# blds.net
KiCad netlist of a schematic drawn in Altium Designer
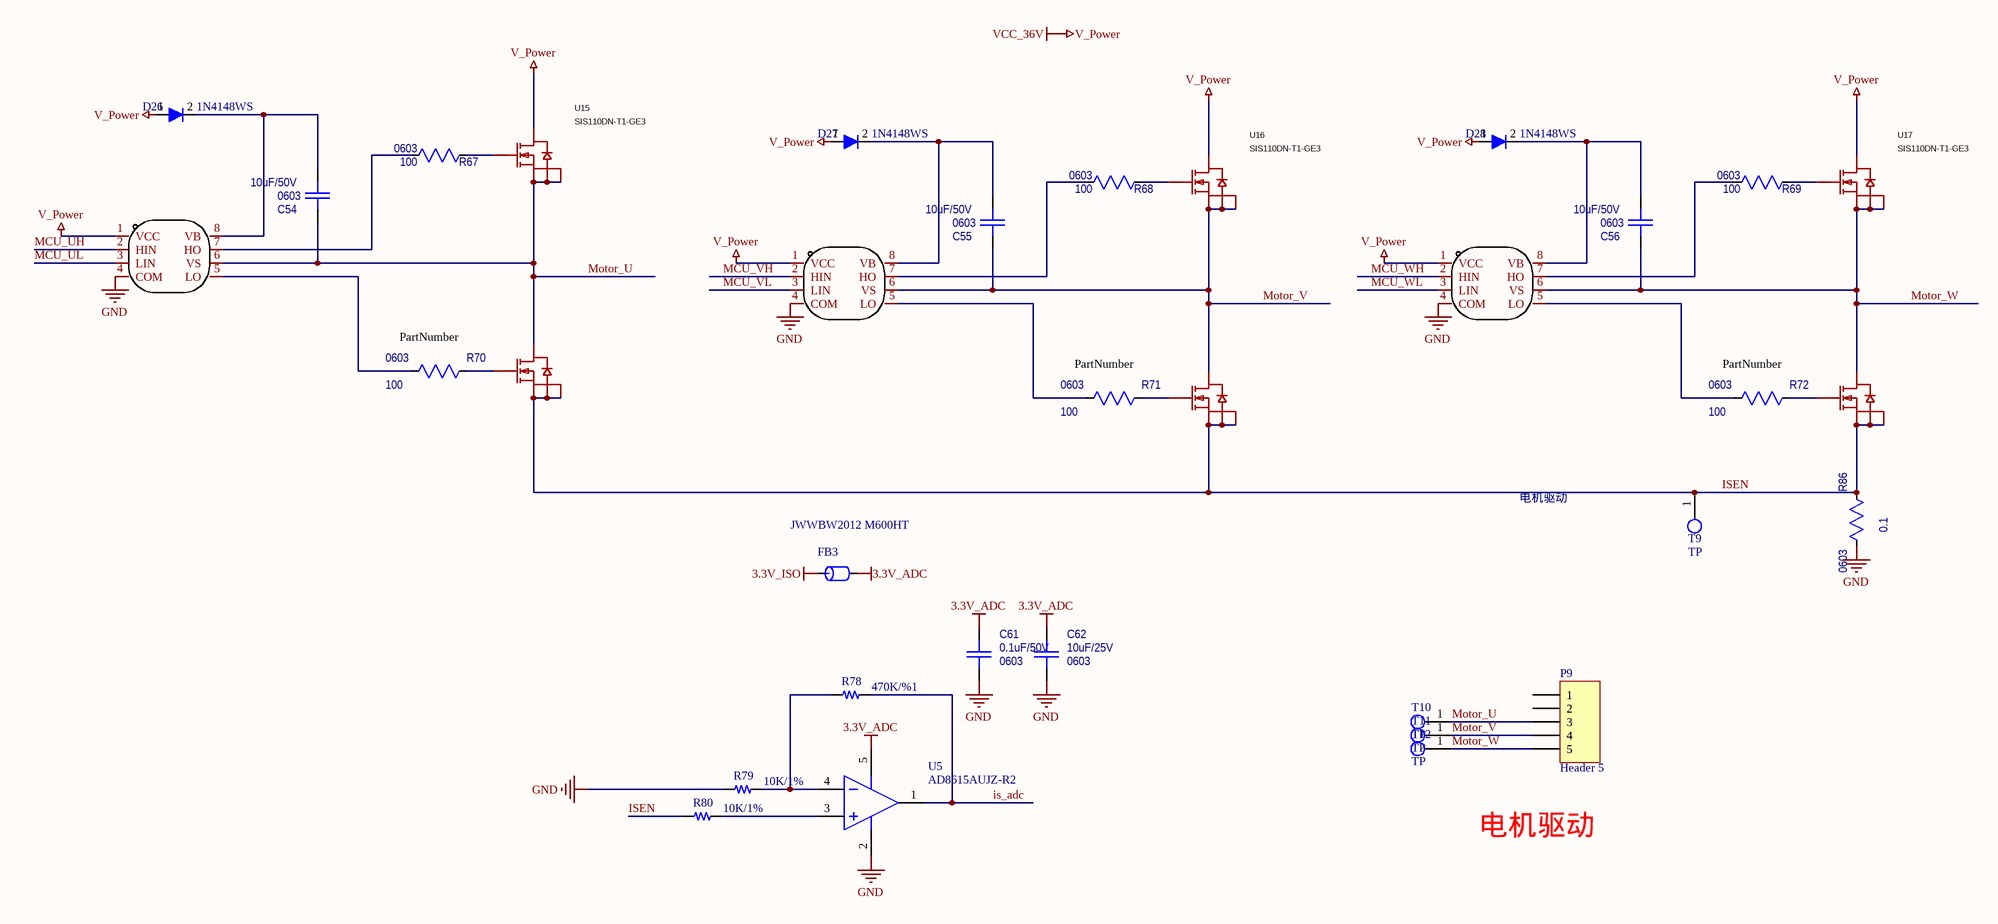
[diagram p0: blds.SchDoc]

(export (version "E")
  (design (tool "Eeschema 10.0.6"))
  (components
    (comp (ref "C54")
      (value "10uF/50V")
      (footprint "CAPC1608X092N_0603")
      (description "Capacitor, MLCC")
      (fields
        (field (name "MANUFACTURER") "muRata")
        (field (name "PARTNUMBER") "GQM2195C2E4R7CB12J")
        (field (name "PACKAGE") "0603")
      )
      (libsource (lib "Karl") (part "Capacitor_0603"))
    )
    (comp (ref "C55")
      (value "10uF/50V")
      (footprint "CAPC1608X092N_0603")
      (description "Capacitor, MLCC")
      (fields
        (field (name "MANUFACTURER") "muRata")
        (field (name "PARTNUMBER") "GQM2195C2E4R7CB12J")
        (field (name "PACKAGE") "0603")
      )
      (libsource (lib "Karl") (part "Capacitor_0603"))
    )
    (comp (ref "C56")
      (value "10uF/50V")
      (footprint "CAPC1608X092N_0603")
      (description "Capacitor, MLCC")
      (fields
        (field (name "MANUFACTURER") "muRata")
        (field (name "PARTNUMBER") "GQM2195C2E4R7CB12J")
        (field (name "PACKAGE") "0603")
      )
      (libsource (lib "Karl") (part "Capacitor_0603"))
    )
    (comp (ref "C61")
      (value "0.1uF/50V")
      (footprint "CAPC1608X092N_0603")
      (fields
        (field (name "PARTNUMBER") "C0603C104M5RACTU")
        (field (name "TOLERANCE") "[tol]")
        (field (name "PACKAGE") "0603")
        (field (name "Comment") "Capacitor_0603")
      )
      (libsource (lib "Karl") (part "Capacitor_0603"))
    )
    (comp (ref "C62")
      (value "10uF/25V")
      (footprint "CAPC1608X092N_0603")
      (fields
        (field (name "PARTNUMBER") "C0603C104M5RACTU")
        (field (name "TOLERANCE") "[tol]")
        (field (name "PACKAGE") "0603")
        (field (name "Comment") "Capacitor_0603")
      )
      (libsource (lib "Karl") (part "Capacitor_0603"))
    )
    (comp (ref "D26") (value "1N4148WS") (footprint "SOD323") (libsource (lib "Device2018") (part "LL4148")))
    (comp (ref "D27") (value "1N4148WS") (footprint "SOD323") (libsource (lib "Device2018") (part "LL4148")))
    (comp (ref "D28") (value "1N4148WS") (footprint "SOD323") (libsource (lib "Device2018") (part "LL4148")))
    (comp (ref "FB3")
      (value "JWWBW2012 M600HT")
      (footprint "0805R")
      (libsource (lib "Schlib_20110825") (part "FB"))
    )
    (comp (ref "P9")
      (value "Header 5")
      (footprint "HDR1X5")
      (description "Header, 5-Pin")
      (fields (field (name "PUBLISHER") "Altium Limited"))
      (libsource (lib "Miscellaneous Connectors") (part "Header 5"))
    )
    (comp (ref "R67")
      (value "100")
      (footprint "RESC1608X055N_0603")
      (description "Resistor, Standard")
      (fields
        (field (name "MANUFACTURER") "Yageo")
        (field (name "PARTNUMBER") "RC0603FR-0710KL")
        (field (name "PACKAGE") "0603")
      )
      (libsource (lib "Karl") (part "Resistor_0603"))
    )
    (comp (ref "R68")
      (value "100")
      (footprint "RESC1608X055N_0603")
      (description "Resistor, Standard")
      (fields
        (field (name "MANUFACTURER") "Yageo")
        (field (name "PARTNUMBER") "RC0603FR-0710KL")
        (field (name "PACKAGE") "0603")
      )
      (libsource (lib "Karl") (part "Resistor_0603"))
    )
    (comp (ref "R69")
      (value "100")
      (footprint "RESC1608X055N_0603")
      (description "Resistor, Standard")
      (fields
        (field (name "MANUFACTURER") "Yageo")
        (field (name "PARTNUMBER") "RC0603FR-0710KL")
        (field (name "PACKAGE") "0603")
      )
      (libsource (lib "Karl") (part "Resistor_0603"))
    )
    (comp (ref "R70")
      (value "100")
      (footprint "RESC1608X055N_0603")
      (description "Resistor, Standard")
      (fields
        (field (name "MANUFACTURER") "Yageo")
        (field (name "PARTNUMBER") "RC0603FR-0710KL")
        (field (name "PACKAGE") "0603")
      )
      (libsource (lib "Karl") (part "Resistor_0603"))
    )
    (comp (ref "R71")
      (value "100")
      (footprint "RESC1608X055N_0603")
      (description "Resistor, Standard")
      (fields
        (field (name "MANUFACTURER") "Yageo")
        (field (name "PARTNUMBER") "RC0603FR-0710KL")
        (field (name "PACKAGE") "0603")
      )
      (libsource (lib "Karl") (part "Resistor_0603"))
    )
    (comp (ref "R72")
      (value "100")
      (footprint "RESC1608X055N_0603")
      (description "Resistor, Standard")
      (fields
        (field (name "MANUFACTURER") "Yageo")
        (field (name "PARTNUMBER") "RC0603FR-0710KL")
        (field (name "PACKAGE") "0603")
      )
      (libsource (lib "Karl") (part "Resistor_0603"))
    )
    (comp (ref "R78") (value "470K/%1") (footprint "0603R") (libsource (lib "JRJ_1") (part "R")))
    (comp (ref "R79") (value "10K/1%") (footprint "0603R") (libsource (lib "JRJ_1") (part "R")))
    (comp (ref "R80") (value "10K/1%") (footprint "0603R") (libsource (lib "JRJ_1") (part "R")))
    (comp (ref "R86")
      (value "0.1")
      (footprint "2010R")
      (description "Resistor, Standard")
      (fields
        (field (name "MANUFACTURER") "Yageo")
        (field (name "PARTNUMBER") "RC0603FR-0710KL")
        (field (name "PACKAGE") "0603")
      )
      (libsource (lib "Karl") (part "Resistor_0603"))
    )
    (comp (ref "T9") (value "TP") (footprint "TPD") (libsource (lib "Schlib_20110825") (part "TP")))
    (comp (ref "T10") (value "TP") (footprint "TPD") (libsource (lib "Schlib_20110825") (part "TP")))
    (comp (ref "T11") (value "TP") (footprint "TPD") (libsource (lib "Schlib_20110825") (part "TP")))
    (comp (ref "T12") (value "TP") (footprint "TPD") (libsource (lib "Schlib_20110825") (part "TP")))
    (comp (ref "U5")
      (value "AD8615AUJZ-R2")
      (footprint "sot-23-5")
      (libsource (lib "Schlib_20110825") (part "AD8615"))
    )
    (comp (ref "U15")
      (value "SIS110DN-T1-GE3")
      (footprint "DFN-8_L3.3-W3.3-P0.65-BL-2")
      (fields (field (name "MANUFACTURER") "VISHAY(威世)"))
      (libsource (lib "altium-import") (part "root_0_SIS110DN-T1-GE3_"))
    )
    (comp (ref "U16")
      (value "SIS110DN-T1-GE3")
      (footprint "DFN-8_L3.3-W3.3-P0.65-BL-2")
      (fields (field (name "MANUFACTURER") "VISHAY(威世)"))
      (libsource (lib "altium-import") (part "root_0_SIS110DN-T1-GE3_"))
    )
    (comp (ref "U17")
      (value "SIS110DN-T1-GE3")
      (footprint "DFN-8_L3.3-W3.3-P0.65-BL-2")
      (fields (field (name "MANUFACTURER") "VISHAY(威世)"))
      (libsource (lib "altium-import") (part "root_0_SIS110DN-T1-GE3_"))
    )
    (comp (ref "U18")
      (value "IRS21867STRPBF")
      (footprint "SO-8")
      (fields (field (name "MANUFACTURER") "Infineon(英飞凌)"))
      (libsource (lib "altium-import") (part "root_0_IRS21867STRPBF_"))
    )
    (comp (ref "U19")
      (value "IRS21867STRPBF")
      (footprint "SO-8")
      (fields (field (name "MANUFACTURER") "Infineon(英飞凌)"))
      (libsource (lib "altium-import") (part "root_0_IRS21867STRPBF_"))
    )
    (comp (ref "U20")
      (value "IRS21867STRPBF")
      (footprint "SO-8")
      (fields (field (name "MANUFACTURER") "Infineon(英飞凌)"))
      (libsource (lib "altium-import") (part "root_0_IRS21867STRPBF_"))
    )
    (comp (ref "U21")
      (value "SIS110DN-T1-GE3")
      (footprint "DFN-8_L3.3-W3.3-P0.65-BL-2")
      (fields (field (name "MANUFACTURER") "VISHAY(威世)"))
      (libsource (lib "altium-import") (part "root_0_SIS110DN-T1-GE3_"))
    )
    (comp (ref "U22")
      (value "SIS110DN-T1-GE3")
      (footprint "DFN-8_L3.3-W3.3-P0.65-BL-2")
      (fields (field (name "MANUFACTURER") "VISHAY(威世)"))
      (libsource (lib "altium-import") (part "root_0_SIS110DN-T1-GE3_"))
    )
    (comp (ref "U23")
      (value "SIS110DN-T1-GE3")
      (footprint "DFN-8_L3.3-W3.3-P0.65-BL-2")
      (fields (field (name "MANUFACTURER") "VISHAY(威世)"))
      (libsource (lib "altium-import") (part "root_0_SIS110DN-T1-GE3_"))
    )
  )
  (nets
    (net (code "1") (name "/ISEN") (class "Default")
      (node (ref "R80") (pin "2") (pintype "passive"))
      (node (ref "R86") (pin "2") (pinfunction "2_2") (pintype "passive"))
      (node (ref "T9") (pin "1") (pintype "passive"))
      (node (ref "U21") (pin "1") (pinfunction "S_1") (pintype "passive"))
      (node (ref "U21") (pin "2") (pinfunction "S_2") (pintype "passive"))
      (node (ref "U21") (pin "3") (pinfunction "S_3") (pintype "passive"))
      (node (ref "U22") (pin "1") (pinfunction "S_1") (pintype "passive"))
      (node (ref "U22") (pin "2") (pinfunction "S_2") (pintype "passive"))
      (node (ref "U22") (pin "3") (pinfunction "S_3") (pintype "passive"))
      (node (ref "U23") (pin "1") (pinfunction "S_1") (pintype "passive"))
      (node (ref "U23") (pin "2") (pinfunction "S_2") (pintype "passive"))
      (node (ref "U23") (pin "3") (pinfunction "S_3") (pintype "passive"))
    )
    (net (code "2") (name "/MCU_UH") (class "Default")
      (node (ref "U18") (pin "2") (pinfunction "HIN_2") (pintype "passive"))
    )
    (net (code "3") (name "/MCU_UL") (class "Default")
      (node (ref "U18") (pin "3") (pinfunction "LIN_3") (pintype "passive"))
    )
    (net (code "4") (name "/MCU_VH") (class "Default")
      (node (ref "U19") (pin "2") (pinfunction "HIN_2") (pintype "passive"))
    )
    (net (code "5") (name "/MCU_VL") (class "Default")
      (node (ref "U19") (pin "3") (pinfunction "LIN_3") (pintype "passive"))
    )
    (net (code "6") (name "/MCU_WH") (class "Default")
      (node (ref "U20") (pin "2") (pinfunction "HIN_2") (pintype "passive"))
    )
    (net (code "7") (name "/MCU_WL") (class "Default")
      (node (ref "U20") (pin "3") (pinfunction "LIN_3") (pintype "passive"))
    )
    (net (code "8") (name "/Motor_U") (class "Default")
      (node (ref "C54") (pin "1") (pinfunction "1_1") (pintype "passive"))
      (node (ref "P9") (pin "3") (pinfunction "3_3") (pintype "passive"))
      (node (ref "T10") (pin "1") (pintype "passive"))
      (node (ref "U15") (pin "1") (pinfunction "S_1") (pintype "passive"))
      (node (ref "U15") (pin "2") (pinfunction "S_2") (pintype "passive"))
      (node (ref "U15") (pin "3") (pinfunction "S_3") (pintype "passive"))
      (node (ref "U18") (pin "6") (pinfunction "VS_6") (pintype "passive"))
      (node (ref "U21") (pin "5") (pinfunction "D_5") (pintype "passive"))
    )
    (net (code "9") (name "/Motor_V") (class "Default")
      (node (ref "C55") (pin "1") (pinfunction "1_1") (pintype "passive"))
      (node (ref "P9") (pin "4") (pinfunction "4_4") (pintype "passive"))
      (node (ref "T11") (pin "1") (pintype "passive"))
      (node (ref "U16") (pin "1") (pinfunction "S_1") (pintype "passive"))
      (node (ref "U16") (pin "2") (pinfunction "S_2") (pintype "passive"))
      (node (ref "U16") (pin "3") (pinfunction "S_3") (pintype "passive"))
      (node (ref "U19") (pin "6") (pinfunction "VS_6") (pintype "passive"))
      (node (ref "U22") (pin "5") (pinfunction "D_5") (pintype "passive"))
    )
    (net (code "10") (name "/Motor_W") (class "Default")
      (node (ref "C56") (pin "1") (pinfunction "1_1") (pintype "passive"))
      (node (ref "P9") (pin "5") (pinfunction "5_5") (pintype "passive"))
      (node (ref "T12") (pin "1") (pintype "passive"))
      (node (ref "U17") (pin "1") (pinfunction "S_1") (pintype "passive"))
      (node (ref "U17") (pin "2") (pinfunction "S_2") (pintype "passive"))
      (node (ref "U17") (pin "3") (pinfunction "S_3") (pintype "passive"))
      (node (ref "U20") (pin "6") (pinfunction "VS_6") (pintype "passive"))
      (node (ref "U23") (pin "5") (pinfunction "D_5") (pintype "passive"))
    )
    (net (code "11") (name "/is_adc") (class "Default")
      (node (ref "R78") (pin "1") (pintype "passive"))
      (node (ref "U5") (pin "1") (pinfunction "OS_NUL_1") (pintype "passive"))
    )
    (net (code "12") (name "3.3V_ADC") (class "Default")
      (node (ref "C61") (pin "1") (pinfunction "1_1") (pintype "passive"))
      (node (ref "C62") (pin "1") (pinfunction "1_1") (pintype "passive"))
      (node (ref "FB3") (pin "2") (pintype "passive"))
      (node (ref "U5") (pin "5") (pinfunction "VCC_5") (pintype "passive"))
    )
    (net (code "13") (name "3.3V_ISO") (class "Default") (node (ref "FB3") (pin "1") (pintype "passive")))
    (net (code "14") (name "GND") (class "Default")
      (node (ref "C61") (pin "2") (pinfunction "2_2") (pintype "passive"))
      (node (ref "C62") (pin "2") (pinfunction "2_2") (pintype "passive"))
      (node (ref "R79") (pin "2") (pintype "passive"))
      (node (ref "R86") (pin "1") (pinfunction "1_1") (pintype "passive"))
      (node (ref "U18") (pin "4") (pinfunction "COM_4") (pintype "passive"))
      (node (ref "U19") (pin "4") (pinfunction "COM_4") (pintype "passive"))
      (node (ref "U20") (pin "4") (pinfunction "COM_4") (pintype "passive"))
      (node (ref "U5") (pin "2") (pinfunction "G_2") (pintype "power_in"))
    )
    (net (code "15") (name "Net-(D26-A)") (class "Default")
      (node (ref "C54") (pin "2") (pinfunction "2_2") (pintype "passive"))
      (node (ref "D26") (pin "2") (pinfunction "A_2") (pintype "passive"))
      (node (ref "U18") (pin "8") (pinfunction "VB_8") (pintype "passive"))
    )
    (net (code "16") (name "Net-(D27-A)") (class "Default")
      (node (ref "C55") (pin "2") (pinfunction "2_2") (pintype "passive"))
      (node (ref "D27") (pin "2") (pinfunction "A_2") (pintype "passive"))
      (node (ref "U19") (pin "8") (pinfunction "VB_8") (pintype "passive"))
    )
    (net (code "17") (name "Net-(D28-A)") (class "Default")
      (node (ref "C56") (pin "2") (pinfunction "2_2") (pintype "passive"))
      (node (ref "D28") (pin "2") (pinfunction "A_2") (pintype "passive"))
      (node (ref "U20") (pin "8") (pinfunction "VB_8") (pintype "passive"))
    )
    (net (code "18") (name "Net-(U5-V+)") (class "Default")
      (node (ref "R80") (pin "1") (pintype "passive"))
      (node (ref "U5") (pin "3") (pinfunction "V+_3") (pintype "power_in"))
    )
    (net (code "19") (name "Net-(U5-V-)") (class "Default")
      (node (ref "R78") (pin "2") (pintype "passive"))
      (node (ref "R79") (pin "1") (pintype "passive"))
      (node (ref "U5") (pin "4") (pinfunction "V-_4") (pintype "power_in"))
    )
    (net (code "20") (name "Net-(U15-G)") (class "Default")
      (node (ref "R67") (pin "2") (pinfunction "2_2") (pintype "passive"))
      (node (ref "U15") (pin "4") (pinfunction "G_4") (pintype "passive"))
    )
    (net (code "21") (name "Net-(U16-G)") (class "Default")
      (node (ref "R68") (pin "2") (pinfunction "2_2") (pintype "passive"))
      (node (ref "U16") (pin "4") (pinfunction "G_4") (pintype "passive"))
    )
    (net (code "22") (name "Net-(U17-G)") (class "Default")
      (node (ref "R69") (pin "2") (pinfunction "2_2") (pintype "passive"))
      (node (ref "U17") (pin "4") (pinfunction "G_4") (pintype "passive"))
    )
    (net (code "23") (name "Net-(U18-HO)") (class "Default")
      (node (ref "R67") (pin "1") (pinfunction "1_1") (pintype "passive"))
      (node (ref "U18") (pin "7") (pinfunction "HO_7") (pintype "passive"))
    )
    (net (code "24") (name "Net-(U18-LO)") (class "Default")
      (node (ref "R70") (pin "1") (pinfunction "1_1") (pintype "passive"))
      (node (ref "U18") (pin "5") (pinfunction "LO_5") (pintype "passive"))
    )
    (net (code "25") (name "Net-(U19-HO)") (class "Default")
      (node (ref "R68") (pin "1") (pinfunction "1_1") (pintype "passive"))
      (node (ref "U19") (pin "7") (pinfunction "HO_7") (pintype "passive"))
    )
    (net (code "26") (name "Net-(U19-LO)") (class "Default")
      (node (ref "R71") (pin "1") (pinfunction "1_1") (pintype "passive"))
      (node (ref "U19") (pin "5") (pinfunction "LO_5") (pintype "passive"))
    )
    (net (code "27") (name "Net-(U20-HO)") (class "Default")
      (node (ref "R69") (pin "1") (pinfunction "1_1") (pintype "passive"))
      (node (ref "U20") (pin "7") (pinfunction "HO_7") (pintype "passive"))
    )
    (net (code "28") (name "Net-(U20-LO)") (class "Default")
      (node (ref "R72") (pin "1") (pinfunction "1_1") (pintype "passive"))
      (node (ref "U20") (pin "5") (pinfunction "LO_5") (pintype "passive"))
    )
    (net (code "29") (name "Net-(U21-G)") (class "Default")
      (node (ref "R70") (pin "2") (pinfunction "2_2") (pintype "passive"))
      (node (ref "U21") (pin "4") (pinfunction "G_4") (pintype "passive"))
    )
    (net (code "30") (name "Net-(U22-G)") (class "Default")
      (node (ref "R71") (pin "2") (pinfunction "2_2") (pintype "passive"))
      (node (ref "U22") (pin "4") (pinfunction "G_4") (pintype "passive"))
    )
    (net (code "31") (name "Net-(U23-G)") (class "Default")
      (node (ref "R72") (pin "2") (pinfunction "2_2") (pintype "passive"))
      (node (ref "U23") (pin "4") (pinfunction "G_4") (pintype "passive"))
    )
    (net (code "32") (name "VCC_36V") (class "Default")
      (node (ref "D26") (pin "1") (pinfunction "K_1") (pintype "passive"))
      (node (ref "D27") (pin "1") (pinfunction "K_1") (pintype "passive"))
      (node (ref "D28") (pin "1") (pinfunction "K_1") (pintype "passive"))
      (node (ref "U15") (pin "5") (pinfunction "D_5") (pintype "passive"))
      (node (ref "U16") (pin "5") (pinfunction "D_5") (pintype "passive"))
      (node (ref "U17") (pin "5") (pinfunction "D_5") (pintype "passive"))
      (node (ref "U18") (pin "1") (pinfunction "VCC_1") (pintype "passive"))
      (node (ref "U19") (pin "1") (pinfunction "VCC_1") (pintype "passive"))
      (node (ref "U20") (pin "1") (pinfunction "VCC_1") (pintype "passive"))
    )
    (net (code "33") (name "unconnected-(P9-Pad1)") (class "Default")
      (node (ref "P9") (pin "1") (pinfunction "1_1") (pintype "passive"))
    )
    (net (code "34") (name "unconnected-(P9-Pad2)") (class "Default")
      (node (ref "P9") (pin "2") (pinfunction "2_2") (pintype "passive"))
    )
  )
)
